# Regulators.net
KiCad netlist of a schematic drawn in Altium Designer
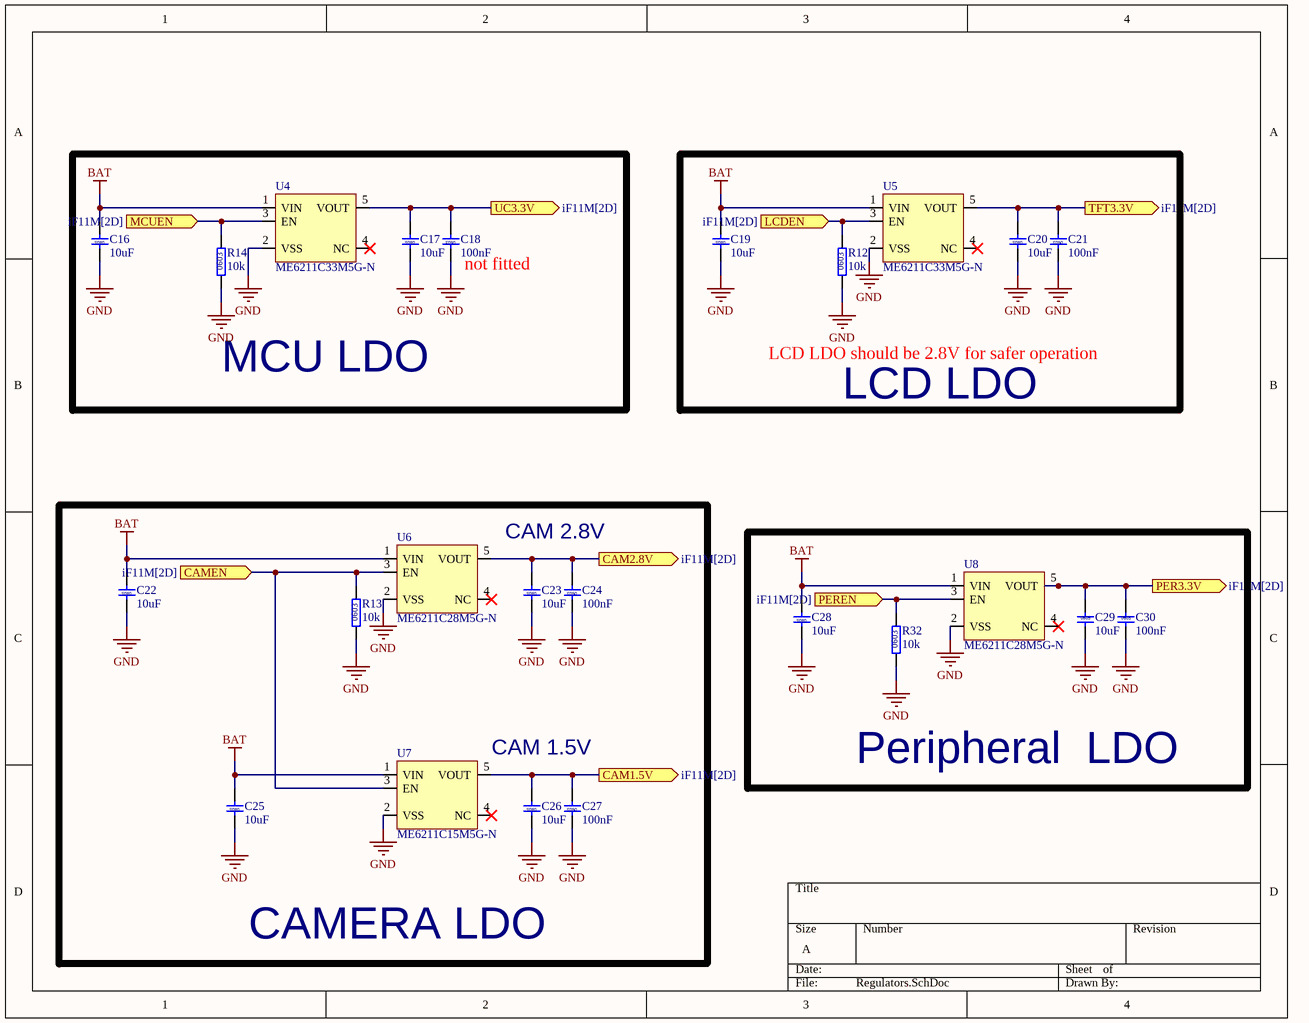
[diagram p0: Regulators.SchDoc]

(export (version "E")
  (design (tool "Eeschema 10.0.6"))
  (components
    (comp (ref "C16")
      (value "10uF")
      (footprint "C0805")
      (description "10% 25V")
      (fields (field (name "PART NO") "WP0005368"))
      (libsource (lib "Rescap") (part "C 0805 10uF 25V"))
    )
    (comp (ref "C17")
      (value "10uF")
      (footprint "C0805")
      (description "10% 25V")
      (fields (field (name "PART NO") "WP0005368"))
      (libsource (lib "Rescap") (part "C 0805 10uF 25V"))
    )
    (comp (ref "C18")
      (value "100nF")
      (footprint "C0603")
      (description "10% 50V")
      (fields (field (name "PART NO") "W-T-CA-X703N100K50VNT") (field (name "MANUFACTURER") "FENGHUA"))
      (libsource (lib "Rescap") (part "C 0603 100nF 50V"))
    )
    (comp (ref "C19")
      (value "10uF")
      (footprint "C0805")
      (description "10% 25V")
      (fields (field (name "PART NO") "WP0005368"))
      (libsource (lib "Rescap") (part "C 0805 10uF 25V"))
    )
    (comp (ref "C20")
      (value "10uF")
      (footprint "C0805")
      (description "10% 25V")
      (fields (field (name "PART NO") "WP0005368"))
      (libsource (lib "Rescap") (part "C 0805 10uF 25V"))
    )
    (comp (ref "C21")
      (value "100nF")
      (footprint "C0603")
      (description "10% 50V")
      (fields (field (name "PART NO") "W-T-CA-X703N100K50VNT") (field (name "MANUFACTURER") "FENGHUA"))
      (libsource (lib "Rescap") (part "C 0603 100nF 50V"))
    )
    (comp (ref "C22")
      (value "10uF")
      (footprint "C0805")
      (description "10% 25V")
      (fields (field (name "PART NO") "WP0005368"))
      (libsource (lib "Rescap") (part "C 0805 10uF 25V"))
    )
    (comp (ref "C23")
      (value "10uF")
      (footprint "C0805")
      (description "10% 25V")
      (fields (field (name "PART NO") "WP0005368"))
      (libsource (lib "Rescap") (part "C 0805 10uF 25V"))
    )
    (comp (ref "C24")
      (value "100nF")
      (footprint "C0603")
      (description "10% 50V")
      (fields (field (name "PART NO") "W-T-CA-X703N100K50VNT") (field (name "MANUFACTURER") "FENGHUA"))
      (libsource (lib "Rescap") (part "C 0603 100nF 50V"))
    )
    (comp (ref "C25")
      (value "10uF")
      (footprint "C0805")
      (description "10% 25V")
      (fields (field (name "PART NO") "WP0005368"))
      (libsource (lib "Rescap") (part "C 0805 10uF 25V"))
    )
    (comp (ref "C26")
      (value "10uF")
      (footprint "C0805")
      (description "10% 25V")
      (fields (field (name "PART NO") "WP0005368"))
      (libsource (lib "Rescap") (part "C 0805 10uF 25V"))
    )
    (comp (ref "C27")
      (value "100nF")
      (footprint "C0603")
      (description "10% 50V")
      (fields (field (name "PART NO") "W-T-CA-X703N100K50VNT") (field (name "MANUFACTURER") "FENGHUA"))
      (libsource (lib "Rescap") (part "C 0603 100nF 50V"))
    )
    (comp (ref "C28")
      (value "10uF")
      (footprint "C0805")
      (description "10% 25V")
      (fields (field (name "PART NO") "WP0005368"))
      (libsource (lib "Rescap") (part "C 0805 10uF 25V"))
    )
    (comp (ref "C29")
      (value "10uF")
      (footprint "C0805")
      (description "10% 25V")
      (fields (field (name "PART NO") "WP0005368"))
      (libsource (lib "Rescap") (part "C 0805 10uF 25V"))
    )
    (comp (ref "C30")
      (value "100nF")
      (footprint "C0603")
      (description "10% 50V")
      (fields (field (name "PART NO") "W-T-CA-X703N100K50VNT") (field (name "MANUFACTURER") "FENGHUA"))
      (libsource (lib "Rescap") (part "C 0603 100nF 50V"))
    )
    (comp (ref "R12")
      (value "10k")
      (footprint "R0603-LD")
      (description "5%")
      (fields (field (name "PART NO") "W-T-RE-RS03K103JT") (field (name "MANUFACTURER") "热敏D541V11增加1颗用量"))
      (libsource (lib "Rescap") (part "R 0603 10k"))
    )
    (comp (ref "R13")
      (value "10k")
      (footprint "R0603-LD")
      (description "5%")
      (fields (field (name "PART NO") "W-T-RE-RS03K103JT") (field (name "MANUFACTURER") "热敏D541V11增加1颗用量"))
      (libsource (lib "Rescap") (part "R 0603 10k"))
    )
    (comp (ref "R14")
      (value "10k")
      (footprint "R0603-LD")
      (description "5%")
      (fields (field (name "PART NO") "W-T-RE-RS03K103JT") (field (name "MANUFACTURER") "热敏D541V11增加1颗用量"))
      (libsource (lib "Rescap") (part "R 0603 10k"))
    )
    (comp (ref "R32")
      (value "10k")
      (footprint "R0603-LD")
      (description "5%")
      (fields (field (name "PART NO") "W-T-RE-RS03K103JT") (field (name "MANUFACTURER") "热敏D541V11增加1颗用量"))
      (libsource (lib "Rescap") (part "R 0603 10k"))
    )
    (comp (ref "U4")
      (value "ME6211C33M5G-N")
      (footprint "SOT23-5")
      (libsource (lib "Others") (part "ME6211C28M5G"))
    )
    (comp (ref "U5")
      (value "ME6211C33M5G-N")
      (footprint "SOT23-5")
      (libsource (lib "Others") (part "ME6211C28M5G"))
    )
    (comp (ref "U6")
      (value "ME6211C28M5G-N")
      (footprint "SOT23-5")
      (libsource (lib "Others") (part "ME6211C28M5G"))
    )
    (comp (ref "U7")
      (value "ME6211C15M5G-N")
      (footprint "SOT23-5")
      (libsource (lib "Others") (part "ME6211C28M5G"))
    )
    (comp (ref "U8")
      (value "ME6211C28M5G-N")
      (footprint "SOT23-5")
      (libsource (lib "Others") (part "ME6211C28M5G"))
    )
  )
  (nets
    (net (code "1") (name "/CAM1.5V") (class "Default")
      (node (ref "C26") (pin "2") (pinfunction "2_2") (pintype "passive"))
      (node (ref "C27") (pin "2") (pinfunction "2_2") (pintype "passive"))
      (node (ref "U7") (pin "5") (pinfunction "VOUT_5") (pintype "passive"))
    )
    (net (code "2") (name "/CAM2.8V") (class "Default")
      (node (ref "C23") (pin "2") (pinfunction "2_2") (pintype "passive"))
      (node (ref "C24") (pin "2") (pinfunction "2_2") (pintype "passive"))
      (node (ref "U6") (pin "5") (pinfunction "VOUT_5") (pintype "passive"))
    )
    (net (code "3") (name "/CAMEN") (class "Default")
      (node (ref "R13") (pin "2") (pinfunction "2_2") (pintype "passive"))
      (node (ref "U6") (pin "3") (pinfunction "EN_3") (pintype "passive"))
      (node (ref "U7") (pin "3") (pinfunction "EN_3") (pintype "passive"))
    )
    (net (code "4") (name "/LCDEN") (class "Default")
      (node (ref "R12") (pin "2") (pinfunction "2_2") (pintype "passive"))
      (node (ref "U5") (pin "3") (pinfunction "EN_3") (pintype "passive"))
    )
    (net (code "5") (name "/MCUEN") (class "Default")
      (node (ref "R14") (pin "2") (pinfunction "2_2") (pintype "passive"))
      (node (ref "U4") (pin "3") (pinfunction "EN_3") (pintype "passive"))
    )
    (net (code "6") (name "/PER3.3V") (class "Default")
      (node (ref "C29") (pin "1") (pinfunction "1_1") (pintype "passive"))
      (node (ref "C30") (pin "1") (pinfunction "1_1") (pintype "passive"))
      (node (ref "U8") (pin "5") (pinfunction "VOUT_5") (pintype "passive"))
    )
    (net (code "7") (name "/PEREN") (class "Default")
      (node (ref "R32") (pin "2") (pinfunction "2_2") (pintype "passive"))
      (node (ref "U8") (pin "3") (pinfunction "EN_3") (pintype "passive"))
    )
    (net (code "8") (name "/TFT3.3V") (class "Default")
      (node (ref "C20") (pin "2") (pinfunction "2_2") (pintype "passive"))
      (node (ref "C21") (pin "2") (pinfunction "2_2") (pintype "passive"))
      (node (ref "U5") (pin "5") (pinfunction "VOUT_5") (pintype "passive"))
    )
    (net (code "9") (name "/UC3.3V") (class "Default")
      (node (ref "C17") (pin "2") (pinfunction "2_2") (pintype "passive"))
      (node (ref "C18") (pin "2") (pinfunction "2_2") (pintype "passive"))
      (node (ref "U4") (pin "5") (pinfunction "VOUT_5") (pintype "passive"))
    )
    (net (code "10") (name "BAT") (class "Default")
      (node (ref "C16") (pin "2") (pinfunction "2_2") (pintype "passive"))
      (node (ref "C19") (pin "2") (pinfunction "2_2") (pintype "passive"))
      (node (ref "C22") (pin "2") (pinfunction "2_2") (pintype "passive"))
      (node (ref "C25") (pin "2") (pinfunction "2_2") (pintype "passive"))
      (node (ref "C28") (pin "2") (pinfunction "2_2") (pintype "passive"))
      (node (ref "U4") (pin "1") (pinfunction "VIN_1") (pintype "passive"))
      (node (ref "U5") (pin "1") (pinfunction "VIN_1") (pintype "passive"))
      (node (ref "U6") (pin "1") (pinfunction "VIN_1") (pintype "passive"))
      (node (ref "U7") (pin "1") (pinfunction "VIN_1") (pintype "passive"))
      (node (ref "U8") (pin "1") (pinfunction "VIN_1") (pintype "passive"))
    )
    (net (code "11") (name "GND") (class "Default")
      (node (ref "C16") (pin "1") (pinfunction "1_1") (pintype "passive"))
      (node (ref "C17") (pin "1") (pinfunction "1_1") (pintype "passive"))
      (node (ref "C18") (pin "1") (pinfunction "1_1") (pintype "passive"))
      (node (ref "C19") (pin "1") (pinfunction "1_1") (pintype "passive"))
      (node (ref "C20") (pin "1") (pinfunction "1_1") (pintype "passive"))
      (node (ref "C21") (pin "1") (pinfunction "1_1") (pintype "passive"))
      (node (ref "C22") (pin "1") (pinfunction "1_1") (pintype "passive"))
      (node (ref "C23") (pin "1") (pinfunction "1_1") (pintype "passive"))
      (node (ref "C24") (pin "1") (pinfunction "1_1") (pintype "passive"))
      (node (ref "C25") (pin "1") (pinfunction "1_1") (pintype "passive"))
      (node (ref "C26") (pin "1") (pinfunction "1_1") (pintype "passive"))
      (node (ref "C27") (pin "1") (pinfunction "1_1") (pintype "passive"))
      (node (ref "C28") (pin "1") (pinfunction "1_1") (pintype "passive"))
      (node (ref "C29") (pin "2") (pinfunction "2_2") (pintype "passive"))
      (node (ref "C30") (pin "2") (pinfunction "2_2") (pintype "passive"))
      (node (ref "R12") (pin "1") (pinfunction "1_1") (pintype "passive"))
      (node (ref "R13") (pin "1") (pinfunction "1_1") (pintype "passive"))
      (node (ref "R14") (pin "1") (pinfunction "1_1") (pintype "passive"))
      (node (ref "R32") (pin "1") (pinfunction "1_1") (pintype "passive"))
      (node (ref "U4") (pin "2") (pinfunction "VSS_2") (pintype "passive"))
      (node (ref "U5") (pin "2") (pinfunction "VSS_2") (pintype "passive"))
      (node (ref "U6") (pin "2") (pinfunction "VSS_2") (pintype "passive"))
      (node (ref "U7") (pin "2") (pinfunction "VSS_2") (pintype "passive"))
      (node (ref "U8") (pin "2") (pinfunction "VSS_2") (pintype "passive"))
    )
    (net (code "12") (name "unconnected-(U4-NC-Pad4)") (class "Default")
      (node (ref "U4") (pin "4") (pinfunction "NC_4") (pintype "passive+no_connect"))
    )
    (net (code "13") (name "unconnected-(U5-NC-Pad4)") (class "Default")
      (node (ref "U5") (pin "4") (pinfunction "NC_4") (pintype "passive+no_connect"))
    )
    (net (code "14") (name "unconnected-(U6-NC-Pad4)") (class "Default")
      (node (ref "U6") (pin "4") (pinfunction "NC_4") (pintype "passive+no_connect"))
    )
    (net (code "15") (name "unconnected-(U7-NC-Pad4)") (class "Default")
      (node (ref "U7") (pin "4") (pinfunction "NC_4") (pintype "passive+no_connect"))
    )
    (net (code "16") (name "unconnected-(U8-NC-Pad4)") (class "Default")
      (node (ref "U8") (pin "4") (pinfunction "NC_4") (pintype "passive+no_connect"))
    )
  )
)
